# IAS_v005.net
KiCad netlist of a schematic drawn in EAGLE
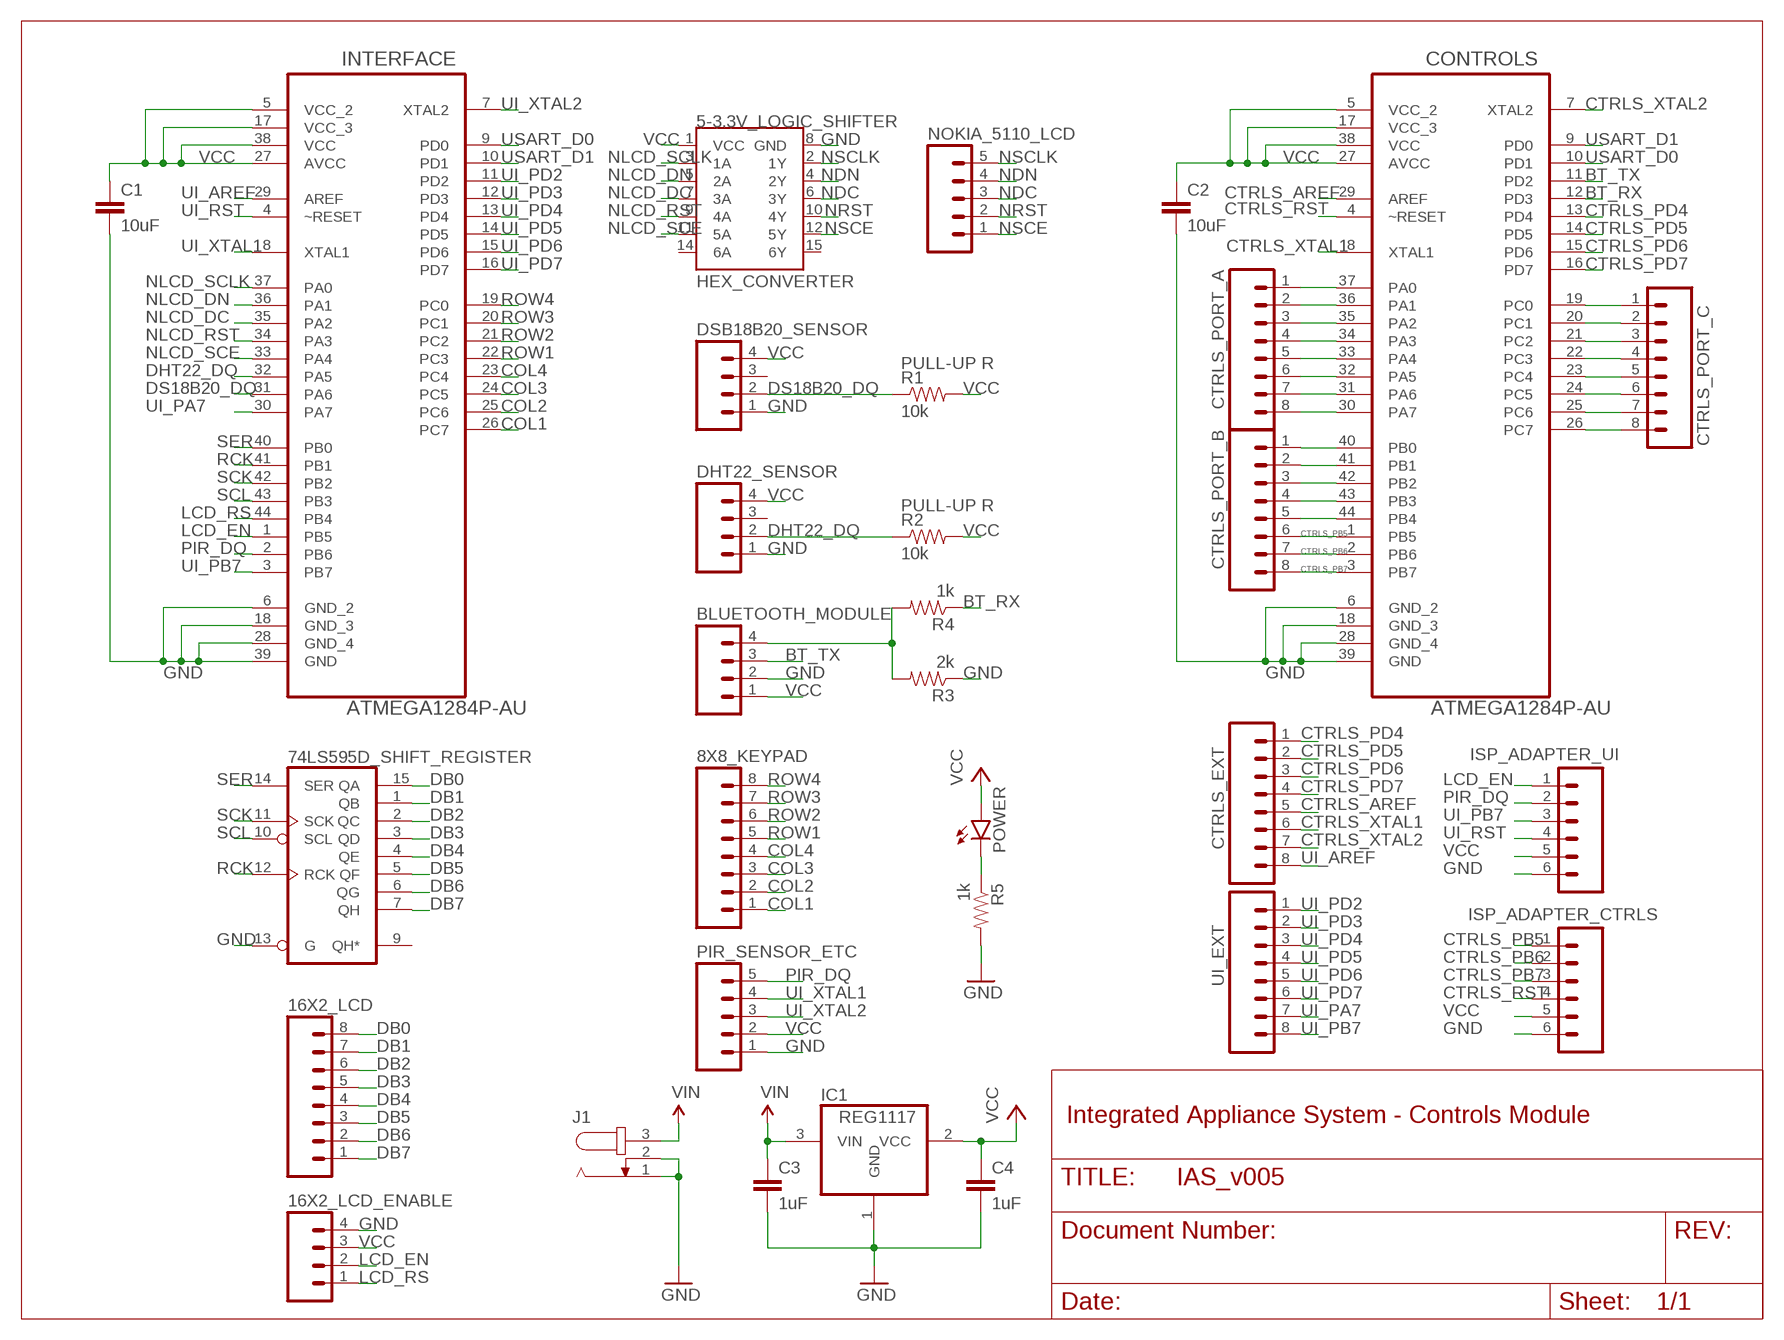
[diagram p0: schematic, sheet 1]

(export (version "E")
  (design (tool "Eeschema 10.0.6"))
  (components
    (comp (ref "5-3.3V_LOGIC_SHIFTER")
      (value "HEX_CONVERTER")
      (footprint "eagle-import:SO016")
      (fields (field (name "MPN") "74HC4050D,652"))
      (libsource (lib "eagle-import") (part "HEX_CONVERTER"))
    )
    (comp (ref "8X8_KEYPAD")
      (value "M08")
      (footprint "eagle-import:1X08_ROUND")
      (libsource (lib "eagle-import") (part "M08"))
    )
    (comp (ref "16X2_LCD")
      (value "M08")
      (footprint "eagle-import:1X08_ROUND")
      (libsource (lib "eagle-import") (part "M08"))
    )
    (comp (ref "16X2_LCD_ENABLE")
      (value "M04NO_SILK_ALL_ROUND")
      (footprint "eagle-import:1X04_NO_SILK_ALL_ROUND")
      (libsource (lib "eagle-import") (part "M04NO_SILK_ALL_ROUND"))
    )
    (comp (ref "74LS595D_SHIFT_REGISTER")
      (value "74LS595D")
      (footprint "eagle-import:SO16")
      (fields (field (name "MPN") "SN74LS595D"))
      (libsource (lib "eagle-import") (part "74595DLS"))
    )
    (comp (ref "BLUETOOTH_MODULE")
      (value "M04NO_SILK_ALL_ROUND")
      (footprint "eagle-import:1X04_NO_SILK_ALL_ROUND")
      (libsource (lib "eagle-import") (part "M04NO_SILK_ALL_ROUND"))
    )
    (comp (ref "C1")
      (value "10uF")
      (footprint "eagle-import:1206")
      (libsource (lib "eagle-import") (part "CAP1206"))
    )
    (comp (ref "C2")
      (value "10uF")
      (footprint "eagle-import:1206")
      (libsource (lib "eagle-import") (part "CAP1206"))
    )
    (comp (ref "C3")
      (value "1uF")
      (footprint "eagle-import:1206")
      (libsource (lib "eagle-import") (part "CAP1206"))
    )
    (comp (ref "C4")
      (value "1uF")
      (footprint "eagle-import:1206")
      (libsource (lib "eagle-import") (part "CAP1206"))
    )
    (comp (ref "CONTROLS")
      (value "ATMEGA1284P-AU")
      (footprint "eagle-import:QFP80P1200X1200X120-44N")
      (fields (field (name "OC_NEWARK") "unknown"))
      (libsource (lib "eagle-import") (part "ATMEGA1284P-AU"))
    )
    (comp (ref "CTRLS_EXT")
      (value "M08")
      (footprint "eagle-import:1X08_ROUND")
      (libsource (lib "eagle-import") (part "M08"))
    )
    (comp (ref "CTRLS_PORT_A")
      (value "M08")
      (footprint "eagle-import:1X08_ROUND")
      (libsource (lib "eagle-import") (part "M08"))
    )
    (comp (ref "CTRLS_PORT_B")
      (value "M08")
      (footprint "eagle-import:1X08_ROUND")
      (libsource (lib "eagle-import") (part "M08"))
    )
    (comp (ref "CTRLS_PORT_C")
      (value "M08")
      (footprint "eagle-import:1X08_ROUND")
      (libsource (lib "eagle-import") (part "M08"))
    )
    (comp (ref "DHT22_SENSOR")
      (value "M04NO_SILK_ALL_ROUND")
      (footprint "eagle-import:1X04_NO_SILK_ALL_ROUND")
      (libsource (lib "eagle-import") (part "M04NO_SILK_ALL_ROUND"))
    )
    (comp (ref "DSB18B20_SENSOR")
      (value "M04NO_SILK_ALL_ROUND")
      (footprint "eagle-import:1X04_NO_SILK_ALL_ROUND")
      (libsource (lib "eagle-import") (part "M04NO_SILK_ALL_ROUND"))
    )
    (comp (ref "IC1")
      (value "REG1117")
      (footprint "eagle-import:SOT223")
      (libsource (lib "eagle-import") (part "REG1117"))
    )
    (comp (ref "INTERFACE")
      (value "ATMEGA1284P-AU")
      (footprint "eagle-import:QFP80P1200X1200X120-44N")
      (fields (field (name "OC_NEWARK") "unknown"))
      (libsource (lib "eagle-import") (part "ATMEGA1284P-AU"))
    )
    (comp (ref "ISP_ADAPTER_CTRLS")
      (value "M06SILK_FEMALE_PTH")
      (footprint "eagle-import:1X06")
      (libsource (lib "eagle-import") (part "M06SILK_FEMALE_PTH"))
    )
    (comp (ref "ISP_ADAPTER_UI")
      (value "M06SILK_FEMALE_PTH")
      (footprint "eagle-import:1X06")
      (libsource (lib "eagle-import") (part "M06SILK_FEMALE_PTH"))
    )
    (comp (ref "J1")
      (value "JACK-PLUG0")
      (footprint "eagle-import:SPC4077")
      (libsource (lib "eagle-import") (part "JACK-PLUG0"))
    )
    (comp (ref "NOKIA_5110_LCD")
      (value "M05PTH")
      (footprint "eagle-import:1X05")
      (libsource (lib "eagle-import") (part "M05PTH"))
    )
    (comp (ref "PIR_SENSOR_ETC")
      (value "M05PTH")
      (footprint "eagle-import:1X05")
      (libsource (lib "eagle-import") (part "M05PTH"))
    )
    (comp (ref "POWER")
      (value "LED3MM")
      (footprint "eagle-import:LED3MM")
      (libsource (lib "eagle-import") (part "LED3MM"))
    )
    (comp (ref "R1")
      (value "10k")
      (footprint "eagle-import:1206")
      (libsource (lib "eagle-import") (part "RESISTOR1206"))
    )
    (comp (ref "R2")
      (value "10k")
      (footprint "eagle-import:1206")
      (libsource (lib "eagle-import") (part "RESISTOR1206"))
    )
    (comp (ref "R3")
      (value "2k")
      (footprint "eagle-import:1206")
      (libsource (lib "eagle-import") (part "RESISTOR1206"))
    )
    (comp (ref "R4")
      (value "1k")
      (footprint "eagle-import:1206")
      (libsource (lib "eagle-import") (part "RESISTOR1206"))
    )
    (comp (ref "R5")
      (value "1k")
      (footprint "eagle-import:1206")
      (libsource (lib "eagle-import") (part "RESISTOR1206"))
    )
    (comp (ref "UI_EXT")
      (value "M08")
      (footprint "eagle-import:1X08_ROUND")
      (libsource (lib "eagle-import") (part "M08"))
    )
  )
  (nets
    (net (code "1") (name "/BT_RX") (class "Default")
      (node (ref "CONTROLS") (pin "12") (pinfunction "PD3_12") (pintype "bidirectional"))
      (node (ref "R4") (pin "1") (pinfunction "1_1") (pintype "passive"))
    )
    (net (code "2") (name "/BT_TX") (class "Default")
      (node (ref "BLUETOOTH_MODULE") (pin "3") (pinfunction "3_3") (pintype "passive"))
      (node (ref "CONTROLS") (pin "11") (pinfunction "PD2_11") (pintype "bidirectional"))
    )
    (net (code "3") (name "/COL1") (class "Default")
      (node (ref "8X8_KEYPAD") (pin "1") (pinfunction "1_1") (pintype "passive"))
      (node (ref "INTERFACE") (pin "26") (pinfunction "PC7_26") (pintype "bidirectional"))
    )
    (net (code "4") (name "/COL2") (class "Default")
      (node (ref "8X8_KEYPAD") (pin "2") (pinfunction "2_2") (pintype "passive"))
      (node (ref "INTERFACE") (pin "25") (pinfunction "PC6_25") (pintype "bidirectional"))
    )
    (net (code "5") (name "/COL3") (class "Default")
      (node (ref "8X8_KEYPAD") (pin "3") (pinfunction "3_3") (pintype "passive"))
      (node (ref "INTERFACE") (pin "24") (pinfunction "PC5_24") (pintype "bidirectional"))
    )
    (net (code "6") (name "/COL4") (class "Default")
      (node (ref "8X8_KEYPAD") (pin "4") (pinfunction "4_4") (pintype "passive"))
      (node (ref "INTERFACE") (pin "23") (pinfunction "PC4_23") (pintype "bidirectional"))
    )
    (net (code "7") (name "/CTRLS_AREF") (class "Default")
      (node (ref "CONTROLS") (pin "29") (pinfunction "AREF_29") (pintype "input"))
      (node (ref "CTRLS_EXT") (pin "5") (pinfunction "5_5") (pintype "passive"))
    )
    (net (code "8") (name "/CTRLS_PB5") (class "Default")
      (node (ref "CONTROLS") (pin "1") (pinfunction "PB5_1") (pintype "bidirectional"))
      (node (ref "CTRLS_PORT_B") (pin "6") (pinfunction "6_6") (pintype "passive"))
      (node (ref "ISP_ADAPTER_CTRLS") (pin "1") (pinfunction "1_1") (pintype "passive"))
    )
    (net (code "9") (name "/CTRLS_PB6") (class "Default")
      (node (ref "CONTROLS") (pin "2") (pinfunction "PB6_2") (pintype "bidirectional"))
      (node (ref "CTRLS_PORT_B") (pin "7") (pinfunction "7_7") (pintype "passive"))
      (node (ref "ISP_ADAPTER_CTRLS") (pin "2") (pinfunction "2_2") (pintype "passive"))
    )
    (net (code "10") (name "/CTRLS_PB7") (class "Default")
      (node (ref "CONTROLS") (pin "3") (pinfunction "PB7_3") (pintype "bidirectional"))
      (node (ref "CTRLS_PORT_B") (pin "8") (pinfunction "8_8") (pintype "passive"))
      (node (ref "ISP_ADAPTER_CTRLS") (pin "3") (pinfunction "3_3") (pintype "passive"))
    )
    (net (code "11") (name "/CTRLS_PD4") (class "Default")
      (node (ref "CONTROLS") (pin "13") (pinfunction "PD4_13") (pintype "bidirectional"))
      (node (ref "CTRLS_EXT") (pin "1") (pinfunction "1_1") (pintype "passive"))
    )
    (net (code "12") (name "/CTRLS_PD5") (class "Default")
      (node (ref "CONTROLS") (pin "14") (pinfunction "PD5_14") (pintype "bidirectional"))
      (node (ref "CTRLS_EXT") (pin "2") (pinfunction "2_2") (pintype "passive"))
    )
    (net (code "13") (name "/CTRLS_PD6") (class "Default")
      (node (ref "CONTROLS") (pin "15") (pinfunction "PD6_15") (pintype "bidirectional"))
      (node (ref "CTRLS_EXT") (pin "3") (pinfunction "3_3") (pintype "passive"))
    )
    (net (code "14") (name "/CTRLS_PD7") (class "Default")
      (node (ref "CONTROLS") (pin "16") (pinfunction "PD7_16") (pintype "bidirectional"))
      (node (ref "CTRLS_EXT") (pin "4") (pinfunction "4_4") (pintype "passive"))
    )
    (net (code "15") (name "/CTRLS_RST") (class "Default")
      (node (ref "CONTROLS") (pin "4") (pinfunction "~{RESET}_4") (pintype "input"))
      (node (ref "ISP_ADAPTER_CTRLS") (pin "4") (pinfunction "4_4") (pintype "passive"))
    )
    (net (code "16") (name "/CTRLS_XTAL1") (class "Default")
      (node (ref "CONTROLS") (pin "8") (pinfunction "XTAL1_8") (pintype "input"))
      (node (ref "CTRLS_EXT") (pin "6") (pinfunction "6_6") (pintype "passive"))
    )
    (net (code "17") (name "/CTRLS_XTAL2") (class "Default")
      (node (ref "CONTROLS") (pin "7") (pinfunction "XTAL2_7") (pintype "output"))
      (node (ref "CTRLS_EXT") (pin "7") (pinfunction "7_7") (pintype "passive"))
    )
    (net (code "18") (name "/DB0") (class "Default")
      (node (ref "16X2_LCD") (pin "8") (pinfunction "8_8") (pintype "passive"))
      (node (ref "74LS595D_SHIFT_REGISTER") (pin "15") (pinfunction "QA_15") (pintype "tri_state"))
    )
    (net (code "19") (name "/DB1") (class "Default")
      (node (ref "16X2_LCD") (pin "7") (pinfunction "7_7") (pintype "passive"))
      (node (ref "74LS595D_SHIFT_REGISTER") (pin "1") (pinfunction "QB_1") (pintype "tri_state"))
    )
    (net (code "20") (name "/DB2") (class "Default")
      (node (ref "16X2_LCD") (pin "6") (pinfunction "6_6") (pintype "passive"))
      (node (ref "74LS595D_SHIFT_REGISTER") (pin "2") (pinfunction "QC_2") (pintype "tri_state"))
    )
    (net (code "21") (name "/DB3") (class "Default")
      (node (ref "16X2_LCD") (pin "5") (pinfunction "5_5") (pintype "passive"))
      (node (ref "74LS595D_SHIFT_REGISTER") (pin "3") (pinfunction "QD_3") (pintype "tri_state"))
    )
    (net (code "22") (name "/DB4") (class "Default")
      (node (ref "16X2_LCD") (pin "4") (pinfunction "4_4") (pintype "passive"))
      (node (ref "74LS595D_SHIFT_REGISTER") (pin "4") (pinfunction "QE_4") (pintype "tri_state"))
    )
    (net (code "23") (name "/DB5") (class "Default")
      (node (ref "16X2_LCD") (pin "3") (pinfunction "3_3") (pintype "passive"))
      (node (ref "74LS595D_SHIFT_REGISTER") (pin "5") (pinfunction "QF_5") (pintype "tri_state"))
    )
    (net (code "24") (name "/DB6") (class "Default")
      (node (ref "16X2_LCD") (pin "2") (pinfunction "2_2") (pintype "passive"))
      (node (ref "74LS595D_SHIFT_REGISTER") (pin "6") (pinfunction "QG_6") (pintype "tri_state"))
    )
    (net (code "25") (name "/DB7") (class "Default")
      (node (ref "16X2_LCD") (pin "1") (pinfunction "1_1") (pintype "passive"))
      (node (ref "74LS595D_SHIFT_REGISTER") (pin "7") (pinfunction "QH_7") (pintype "tri_state"))
    )
    (net (code "26") (name "/DHT22_DQ") (class "Default")
      (node (ref "DHT22_SENSOR") (pin "2") (pinfunction "2_2") (pintype "passive"))
      (node (ref "INTERFACE") (pin "32") (pinfunction "PA5_32") (pintype "bidirectional"))
      (node (ref "R2") (pin "1") (pinfunction "1_1") (pintype "passive"))
    )
    (net (code "27") (name "/DS18B20_DQ") (class "Default")
      (node (ref "DSB18B20_SENSOR") (pin "2") (pinfunction "2_2") (pintype "passive"))
      (node (ref "INTERFACE") (pin "31") (pinfunction "PA6_31") (pintype "bidirectional"))
      (node (ref "R1") (pin "1") (pinfunction "1_1") (pintype "passive"))
    )
    (net (code "28") (name "/LCD_EN") (class "Default")
      (node (ref "16X2_LCD_ENABLE") (pin "2") (pinfunction "2_2") (pintype "passive"))
      (node (ref "INTERFACE") (pin "1") (pinfunction "PB5_1") (pintype "bidirectional"))
      (node (ref "ISP_ADAPTER_UI") (pin "1") (pinfunction "1_1") (pintype "passive"))
    )
    (net (code "29") (name "/LCD_RS") (class "Default")
      (node (ref "16X2_LCD_ENABLE") (pin "1") (pinfunction "1_1") (pintype "passive"))
      (node (ref "INTERFACE") (pin "44") (pinfunction "PB4_44") (pintype "bidirectional"))
    )
    (net (code "30") (name "/NDC") (class "Default")
      (node (ref "5-3.3V_LOGIC_SHIFTER") (pin "6") (pinfunction "3Y_6") (pintype "bidirectional"))
      (node (ref "NOKIA_5110_LCD") (pin "3") (pinfunction "3_3") (pintype "passive"))
    )
    (net (code "31") (name "/NDN") (class "Default")
      (node (ref "5-3.3V_LOGIC_SHIFTER") (pin "4") (pinfunction "2Y_4") (pintype "bidirectional"))
      (node (ref "NOKIA_5110_LCD") (pin "4") (pinfunction "4_4") (pintype "passive"))
    )
    (net (code "32") (name "/NLCD_DC") (class "Default")
      (node (ref "5-3.3V_LOGIC_SHIFTER") (pin "7") (pinfunction "3A_7") (pintype "bidirectional"))
      (node (ref "INTERFACE") (pin "35") (pinfunction "PA2_35") (pintype "bidirectional"))
    )
    (net (code "33") (name "/NLCD_DN") (class "Default")
      (node (ref "5-3.3V_LOGIC_SHIFTER") (pin "5") (pinfunction "2A_5") (pintype "bidirectional"))
      (node (ref "INTERFACE") (pin "36") (pinfunction "PA1_36") (pintype "bidirectional"))
    )
    (net (code "34") (name "/NLCD_RST") (class "Default")
      (node (ref "5-3.3V_LOGIC_SHIFTER") (pin "9") (pinfunction "4A_9") (pintype "bidirectional"))
      (node (ref "INTERFACE") (pin "34") (pinfunction "PA3_34") (pintype "bidirectional"))
    )
    (net (code "35") (name "/NLCD_SCE") (class "Default")
      (node (ref "5-3.3V_LOGIC_SHIFTER") (pin "11") (pinfunction "5A_11") (pintype "bidirectional"))
      (node (ref "INTERFACE") (pin "33") (pinfunction "PA4_33") (pintype "bidirectional"))
    )
    (net (code "36") (name "/NLCD_SCLK") (class "Default")
      (node (ref "5-3.3V_LOGIC_SHIFTER") (pin "3") (pinfunction "1A_3") (pintype "bidirectional"))
      (node (ref "INTERFACE") (pin "37") (pinfunction "PA0_37") (pintype "bidirectional"))
    )
    (net (code "37") (name "/NRST") (class "Default")
      (node (ref "5-3.3V_LOGIC_SHIFTER") (pin "10") (pinfunction "4Y_10") (pintype "bidirectional"))
      (node (ref "NOKIA_5110_LCD") (pin "2") (pinfunction "2_2") (pintype "passive"))
    )
    (net (code "38") (name "/NSCE") (class "Default")
      (node (ref "5-3.3V_LOGIC_SHIFTER") (pin "12") (pinfunction "5Y_12") (pintype "bidirectional"))
      (node (ref "NOKIA_5110_LCD") (pin "1") (pinfunction "1_1") (pintype "passive"))
    )
    (net (code "39") (name "/NSCLK") (class "Default")
      (node (ref "5-3.3V_LOGIC_SHIFTER") (pin "2") (pinfunction "1Y_2") (pintype "bidirectional"))
      (node (ref "NOKIA_5110_LCD") (pin "5") (pinfunction "5_5") (pintype "passive"))
    )
    (net (code "40") (name "/PIR_DQ") (class "Default")
      (node (ref "INTERFACE") (pin "2") (pinfunction "PB6_2") (pintype "bidirectional"))
      (node (ref "ISP_ADAPTER_UI") (pin "2") (pinfunction "2_2") (pintype "passive"))
      (node (ref "PIR_SENSOR_ETC") (pin "5") (pinfunction "5_5") (pintype "passive"))
    )
    (net (code "41") (name "/RCK") (class "Default")
      (node (ref "74LS595D_SHIFT_REGISTER") (pin "12") (pinfunction "RCK_12") (pintype "input"))
      (node (ref "INTERFACE") (pin "41") (pinfunction "PB1_41") (pintype "bidirectional"))
    )
    (net (code "42") (name "/ROW1") (class "Default")
      (node (ref "8X8_KEYPAD") (pin "5") (pinfunction "5_5") (pintype "passive"))
      (node (ref "INTERFACE") (pin "22") (pinfunction "PC3_22") (pintype "bidirectional"))
    )
    (net (code "43") (name "/ROW2") (class "Default")
      (node (ref "8X8_KEYPAD") (pin "6") (pinfunction "6_6") (pintype "passive"))
      (node (ref "INTERFACE") (pin "21") (pinfunction "PC2_21") (pintype "bidirectional"))
    )
    (net (code "44") (name "/ROW3") (class "Default")
      (node (ref "8X8_KEYPAD") (pin "7") (pinfunction "7_7") (pintype "passive"))
      (node (ref "INTERFACE") (pin "20") (pinfunction "PC1_20") (pintype "bidirectional"))
    )
    (net (code "45") (name "/ROW4") (class "Default")
      (node (ref "8X8_KEYPAD") (pin "8") (pinfunction "8_8") (pintype "passive"))
      (node (ref "INTERFACE") (pin "19") (pinfunction "PC0_19") (pintype "bidirectional"))
    )
    (net (code "46") (name "/SCK") (class "Default")
      (node (ref "74LS595D_SHIFT_REGISTER") (pin "11") (pinfunction "SCK_11") (pintype "input"))
      (node (ref "INTERFACE") (pin "42") (pinfunction "PB2_42") (pintype "bidirectional"))
    )
    (net (code "47") (name "/SCL") (class "Default")
      (node (ref "74LS595D_SHIFT_REGISTER") (pin "10") (pinfunction "SCL_10") (pintype "input"))
      (node (ref "INTERFACE") (pin "43") (pinfunction "PB3_43") (pintype "bidirectional"))
    )
    (net (code "48") (name "/SER") (class "Default")
      (node (ref "74LS595D_SHIFT_REGISTER") (pin "14") (pinfunction "SER_14") (pintype "input"))
      (node (ref "INTERFACE") (pin "40") (pinfunction "PB0_40") (pintype "bidirectional"))
    )
    (net (code "49") (name "/UI_AREF") (class "Default")
      (node (ref "CTRLS_EXT") (pin "8") (pinfunction "8_8") (pintype "passive"))
      (node (ref "INTERFACE") (pin "29") (pinfunction "AREF_29") (pintype "input"))
    )
    (net (code "50") (name "/UI_PA7") (class "Default")
      (node (ref "INTERFACE") (pin "30") (pinfunction "PA7_30") (pintype "bidirectional"))
      (node (ref "UI_EXT") (pin "7") (pinfunction "7_7") (pintype "passive"))
    )
    (net (code "51") (name "/UI_PB7") (class "Default")
      (node (ref "INTERFACE") (pin "3") (pinfunction "PB7_3") (pintype "bidirectional"))
      (node (ref "ISP_ADAPTER_UI") (pin "3") (pinfunction "3_3") (pintype "passive"))
      (node (ref "UI_EXT") (pin "8") (pinfunction "8_8") (pintype "passive"))
    )
    (net (code "52") (name "/UI_PD2") (class "Default")
      (node (ref "INTERFACE") (pin "11") (pinfunction "PD2_11") (pintype "bidirectional"))
      (node (ref "UI_EXT") (pin "1") (pinfunction "1_1") (pintype "passive"))
    )
    (net (code "53") (name "/UI_PD3") (class "Default")
      (node (ref "INTERFACE") (pin "12") (pinfunction "PD3_12") (pintype "bidirectional"))
      (node (ref "UI_EXT") (pin "2") (pinfunction "2_2") (pintype "passive"))
    )
    (net (code "54") (name "/UI_PD4") (class "Default")
      (node (ref "INTERFACE") (pin "13") (pinfunction "PD4_13") (pintype "bidirectional"))
      (node (ref "UI_EXT") (pin "3") (pinfunction "3_3") (pintype "passive"))
    )
    (net (code "55") (name "/UI_PD5") (class "Default")
      (node (ref "INTERFACE") (pin "14") (pinfunction "PD5_14") (pintype "bidirectional"))
      (node (ref "UI_EXT") (pin "4") (pinfunction "4_4") (pintype "passive"))
    )
    (net (code "56") (name "/UI_PD6") (class "Default")
      (node (ref "INTERFACE") (pin "15") (pinfunction "PD6_15") (pintype "bidirectional"))
      (node (ref "UI_EXT") (pin "5") (pinfunction "5_5") (pintype "passive"))
    )
    (net (code "57") (name "/UI_PD7") (class "Default")
      (node (ref "INTERFACE") (pin "16") (pinfunction "PD7_16") (pintype "bidirectional"))
      (node (ref "UI_EXT") (pin "6") (pinfunction "6_6") (pintype "passive"))
    )
    (net (code "58") (name "/UI_RST") (class "Default")
      (node (ref "INTERFACE") (pin "4") (pinfunction "~{RESET}_4") (pintype "input"))
      (node (ref "ISP_ADAPTER_UI") (pin "4") (pinfunction "4_4") (pintype "passive"))
    )
    (net (code "59") (name "/UI_XTAL1") (class "Default")
      (node (ref "INTERFACE") (pin "8") (pinfunction "XTAL1_8") (pintype "input"))
      (node (ref "PIR_SENSOR_ETC") (pin "4") (pinfunction "4_4") (pintype "passive"))
    )
    (net (code "60") (name "/UI_XTAL2") (class "Default")
      (node (ref "INTERFACE") (pin "7") (pinfunction "XTAL2_7") (pintype "output"))
      (node (ref "PIR_SENSOR_ETC") (pin "3") (pinfunction "3_3") (pintype "passive"))
    )
    (net (code "61") (name "/USART_D0") (class "Default")
      (node (ref "CONTROLS") (pin "10") (pinfunction "PD1_10") (pintype "bidirectional"))
      (node (ref "INTERFACE") (pin "9") (pinfunction "PD0_9") (pintype "bidirectional"))
    )
    (net (code "62") (name "/USART_D1") (class "Default")
      (node (ref "CONTROLS") (pin "9") (pinfunction "PD0_9") (pintype "bidirectional"))
      (node (ref "INTERFACE") (pin "10") (pinfunction "PD1_10") (pintype "bidirectional"))
    )
    (net (code "63") (name "GND") (class "Default")
      (node (ref "16X2_LCD_ENABLE") (pin "4") (pinfunction "4_4") (pintype "passive"))
      (node (ref "5-3.3V_LOGIC_SHIFTER") (pin "8") (pinfunction "GND_8") (pintype "bidirectional"))
      (node (ref "74LS595D_SHIFT_REGISTER") (pin "13") (pinfunction "G_13") (pintype "input"))
      (node (ref "BLUETOOTH_MODULE") (pin "2") (pinfunction "2_2") (pintype "passive"))
      (node (ref "C1") (pin "2") (pinfunction "2_2") (pintype "passive"))
      (node (ref "C2") (pin "2") (pinfunction "2_2") (pintype "passive"))
      (node (ref "C3") (pin "2") (pinfunction "2_2") (pintype "passive"))
      (node (ref "C4") (pin "2") (pinfunction "2_2") (pintype "passive"))
      (node (ref "CONTROLS") (pin "18") (pinfunction "GND_3_18") (pintype "passive"))
      (node (ref "CONTROLS") (pin "28") (pinfunction "GND_4_28") (pintype "passive"))
      (node (ref "CONTROLS") (pin "39") (pinfunction "GND_39") (pintype "passive"))
      (node (ref "CONTROLS") (pin "6") (pinfunction "GND_2_6") (pintype "passive"))
      (node (ref "DHT22_SENSOR") (pin "1") (pinfunction "1_1") (pintype "passive"))
      (node (ref "DSB18B20_SENSOR") (pin "1") (pinfunction "1_1") (pintype "passive"))
      (node (ref "IC1") (pin "1") (pinfunction "GND_1") (pintype "power_in"))
      (node (ref "INTERFACE") (pin "18") (pinfunction "GND_3_18") (pintype "passive"))
      (node (ref "INTERFACE") (pin "28") (pinfunction "GND_4_28") (pintype "passive"))
      (node (ref "INTERFACE") (pin "39") (pinfunction "GND_39") (pintype "passive"))
      (node (ref "INTERFACE") (pin "6") (pinfunction "GND_2_6") (pintype "passive"))
      (node (ref "ISP_ADAPTER_CTRLS") (pin "6") (pinfunction "6_6") (pintype "passive"))
      (node (ref "ISP_ADAPTER_UI") (pin "6") (pinfunction "6_6") (pintype "passive"))
      (node (ref "J1") (pin "1") (pinfunction "1_1") (pintype "passive"))
      (node (ref "J1") (pin "2") (pinfunction "2_2") (pintype "passive"))
      (node (ref "PIR_SENSOR_ETC") (pin "1") (pinfunction "1_1") (pintype "passive"))
      (node (ref "R3") (pin "1") (pinfunction "1_1") (pintype "passive"))
      (node (ref "R5") (pin "2") (pinfunction "2_2") (pintype "passive"))
    )
    (net (code "64") (name "Net-(BLUETOOTH_MODULE-Pad4)") (class "Default")
      (node (ref "BLUETOOTH_MODULE") (pin "4") (pinfunction "4_4") (pintype "passive"))
      (node (ref "R3") (pin "2") (pinfunction "2_2") (pintype "passive"))
      (node (ref "R4") (pin "2") (pinfunction "2_2") (pintype "passive"))
    )
    (net (code "65") (name "Net-(CONTROLS-PA0)") (class "Default")
      (node (ref "CONTROLS") (pin "37") (pinfunction "PA0_37") (pintype "bidirectional"))
      (node (ref "CTRLS_PORT_A") (pin "1") (pinfunction "1_1") (pintype "passive"))
    )
    (net (code "66") (name "Net-(CONTROLS-PA1)") (class "Default")
      (node (ref "CONTROLS") (pin "36") (pinfunction "PA1_36") (pintype "bidirectional"))
      (node (ref "CTRLS_PORT_A") (pin "2") (pinfunction "2_2") (pintype "passive"))
    )
    (net (code "67") (name "Net-(CONTROLS-PA2)") (class "Default")
      (node (ref "CONTROLS") (pin "35") (pinfunction "PA2_35") (pintype "bidirectional"))
      (node (ref "CTRLS_PORT_A") (pin "3") (pinfunction "3_3") (pintype "passive"))
    )
    (net (code "68") (name "Net-(CONTROLS-PA3)") (class "Default")
      (node (ref "CONTROLS") (pin "34") (pinfunction "PA3_34") (pintype "bidirectional"))
      (node (ref "CTRLS_PORT_A") (pin "4") (pinfunction "4_4") (pintype "passive"))
    )
    (net (code "69") (name "Net-(CONTROLS-PA4)") (class "Default")
      (node (ref "CONTROLS") (pin "33") (pinfunction "PA4_33") (pintype "bidirectional"))
      (node (ref "CTRLS_PORT_A") (pin "5") (pinfunction "5_5") (pintype "passive"))
    )
    (net (code "70") (name "Net-(CONTROLS-PA5)") (class "Default")
      (node (ref "CONTROLS") (pin "32") (pinfunction "PA5_32") (pintype "bidirectional"))
      (node (ref "CTRLS_PORT_A") (pin "6") (pinfunction "6_6") (pintype "passive"))
    )
    (net (code "71") (name "Net-(CONTROLS-PA6)") (class "Default")
      (node (ref "CONTROLS") (pin "31") (pinfunction "PA6_31") (pintype "bidirectional"))
      (node (ref "CTRLS_PORT_A") (pin "7") (pinfunction "7_7") (pintype "passive"))
    )
    (net (code "72") (name "Net-(CONTROLS-PA7)") (class "Default")
      (node (ref "CONTROLS") (pin "30") (pinfunction "PA7_30") (pintype "bidirectional"))
      (node (ref "CTRLS_PORT_A") (pin "8") (pinfunction "8_8") (pintype "passive"))
    )
    (net (code "73") (name "Net-(CONTROLS-PB0)") (class "Default")
      (node (ref "CONTROLS") (pin "40") (pinfunction "PB0_40") (pintype "bidirectional"))
      (node (ref "CTRLS_PORT_B") (pin "1") (pinfunction "1_1") (pintype "passive"))
    )
    (net (code "74") (name "Net-(CONTROLS-PB1)") (class "Default")
      (node (ref "CONTROLS") (pin "41") (pinfunction "PB1_41") (pintype "bidirectional"))
      (node (ref "CTRLS_PORT_B") (pin "2") (pinfunction "2_2") (pintype "passive"))
    )
    (net (code "75") (name "Net-(CONTROLS-PB2)") (class "Default")
      (node (ref "CONTROLS") (pin "42") (pinfunction "PB2_42") (pintype "bidirectional"))
      (node (ref "CTRLS_PORT_B") (pin "3") (pinfunction "3_3") (pintype "passive"))
    )
    (net (code "76") (name "Net-(CONTROLS-PB3)") (class "Default")
      (node (ref "CONTROLS") (pin "43") (pinfunction "PB3_43") (pintype "bidirectional"))
      (node (ref "CTRLS_PORT_B") (pin "4") (pinfunction "4_4") (pintype "passive"))
    )
    (net (code "77") (name "Net-(CONTROLS-PB4)") (class "Default")
      (node (ref "CONTROLS") (pin "44") (pinfunction "PB4_44") (pintype "bidirectional"))
      (node (ref "CTRLS_PORT_B") (pin "5") (pinfunction "5_5") (pintype "passive"))
    )
    (net (code "78") (name "Net-(CONTROLS-PC0)") (class "Default")
      (node (ref "CONTROLS") (pin "19") (pinfunction "PC0_19") (pintype "bidirectional"))
      (node (ref "CTRLS_PORT_C") (pin "1") (pinfunction "1_1") (pintype "passive"))
    )
    (net (code "79") (name "Net-(CONTROLS-PC1)") (class "Default")
      (node (ref "CONTROLS") (pin "20") (pinfunction "PC1_20") (pintype "bidirectional"))
      (node (ref "CTRLS_PORT_C") (pin "2") (pinfunction "2_2") (pintype "passive"))
    )
    (net (code "80") (name "Net-(CONTROLS-PC2)") (class "Default")
      (node (ref "CONTROLS") (pin "21") (pinfunction "PC2_21") (pintype "bidirectional"))
      (node (ref "CTRLS_PORT_C") (pin "3") (pinfunction "3_3") (pintype "passive"))
    )
    (net (code "81") (name "Net-(CONTROLS-PC3)") (class "Default")
      (node (ref "CONTROLS") (pin "22") (pinfunction "PC3_22") (pintype "bidirectional"))
      (node (ref "CTRLS_PORT_C") (pin "4") (pinfunction "4_4") (pintype "passive"))
    )
    (net (code "82") (name "Net-(CONTROLS-PC4)") (class "Default")
      (node (ref "CONTROLS") (pin "23") (pinfunction "PC4_23") (pintype "bidirectional"))
      (node (ref "CTRLS_PORT_C") (pin "5") (pinfunction "5_5") (pintype "passive"))
    )
    (net (code "83") (name "Net-(CONTROLS-PC5)") (class "Default")
      (node (ref "CONTROLS") (pin "24") (pinfunction "PC5_24") (pintype "bidirectional"))
      (node (ref "CTRLS_PORT_C") (pin "6") (pinfunction "6_6") (pintype "passive"))
    )
    (net (code "84") (name "Net-(CONTROLS-PC6)") (class "Default")
      (node (ref "CONTROLS") (pin "25") (pinfunction "PC6_25") (pintype "bidirectional"))
      (node (ref "CTRLS_PORT_C") (pin "7") (pinfunction "7_7") (pintype "passive"))
    )
    (net (code "85") (name "Net-(CONTROLS-PC7)") (class "Default")
      (node (ref "CONTROLS") (pin "26") (pinfunction "PC7_26") (pintype "bidirectional"))
      (node (ref "CTRLS_PORT_C") (pin "8") (pinfunction "8_8") (pintype "passive"))
    )
    (net (code "86") (name "Net-(POWER-C)") (class "Default")
      (node (ref "POWER") (pin "K") (pinfunction "C_K") (pintype "passive"))
      (node (ref "R5") (pin "1") (pinfunction "1_1") (pintype "passive"))
    )
    (net (code "87") (name "VCC") (class "Default")
      (node (ref "16X2_LCD_ENABLE") (pin "3") (pinfunction "3_3") (pintype "passive"))
      (node (ref "5-3.3V_LOGIC_SHIFTER") (pin "1") (pinfunction "VCC_1") (pintype "bidirectional"))
      (node (ref "BLUETOOTH_MODULE") (pin "1") (pinfunction "1_1") (pintype "passive"))
      (node (ref "C1") (pin "1") (pinfunction "1_1") (pintype "passive"))
      (node (ref "C2") (pin "1") (pinfunction "1_1") (pintype "passive"))
      (node (ref "C4") (pin "1") (pinfunction "1_1") (pintype "passive"))
      (node (ref "CONTROLS") (pin "17") (pinfunction "VCC_3_17") (pintype "power_in"))
      (node (ref "CONTROLS") (pin "27") (pinfunction "AVCC_27") (pintype "power_in"))
      (node (ref "CONTROLS") (pin "38") (pinfunction "VCC_38") (pintype "power_in"))
      (node (ref "CONTROLS") (pin "5") (pinfunction "VCC_2_5") (pintype "power_in"))
      (node (ref "DHT22_SENSOR") (pin "4") (pinfunction "4_4") (pintype "passive"))
      (node (ref "DSB18B20_SENSOR") (pin "4") (pinfunction "4_4") (pintype "passive"))
      (node (ref "IC1") (pin "2") (pinfunction "VCC_2") (pintype "power_in"))
      (node (ref "INTERFACE") (pin "17") (pinfunction "VCC_3_17") (pintype "power_in"))
      (node (ref "INTERFACE") (pin "27") (pinfunction "AVCC_27") (pintype "power_in"))
      (node (ref "INTERFACE") (pin "38") (pinfunction "VCC_38") (pintype "power_in"))
      (node (ref "INTERFACE") (pin "5") (pinfunction "VCC_2_5") (pintype "power_in"))
      (node (ref "ISP_ADAPTER_CTRLS") (pin "5") (pinfunction "5_5") (pintype "passive"))
      (node (ref "ISP_ADAPTER_UI") (pin "5") (pinfunction "5_5") (pintype "passive"))
      (node (ref "PIR_SENSOR_ETC") (pin "2") (pinfunction "2_2") (pintype "passive"))
      (node (ref "POWER") (pin "A") (pinfunction "A_A") (pintype "passive"))
      (node (ref "R1") (pin "2") (pinfunction "2_2") (pintype "passive"))
      (node (ref "R2") (pin "2") (pinfunction "2_2") (pintype "passive"))
    )
    (net (code "88") (name "VIN") (class "Default")
      (node (ref "C3") (pin "1") (pinfunction "1_1") (pintype "passive"))
      (node (ref "IC1") (pin "3") (pinfunction "VIN_3") (pintype "input"))
      (node (ref "J1") (pin "3") (pinfunction "3_3") (pintype "passive"))
    )
    (net (code "89") (name "unconnected-(5-3.3V_LOGIC_SHIFTER-6A-Pad14)") (class "Default")
      (node (ref "5-3.3V_LOGIC_SHIFTER") (pin "14") (pinfunction "6A_14") (pintype "bidirectional"))
    )
    (net (code "90") (name "unconnected-(5-3.3V_LOGIC_SHIFTER-6Y-Pad15)") (class "Default")
      (node (ref "5-3.3V_LOGIC_SHIFTER") (pin "15") (pinfunction "6Y_15") (pintype "bidirectional"))
    )
    (net (code "91") (name "unconnected-(74LS595D_SHIFT_REGISTERA-QH*-Pad9)") (class "Default")
      (node (ref "74LS595D_SHIFT_REGISTER") (pin "9") (pinfunction "QH*_9") (pintype "tri_state"))
    )
    (net (code "92") (name "unconnected-(DHT22_SENSOR-Pad3)") (class "Default")
      (node (ref "DHT22_SENSOR") (pin "3") (pinfunction "3_3") (pintype "passive"))
    )
    (net (code "93") (name "unconnected-(DSB18B20_SENSOR-Pad3)") (class "Default")
      (node (ref "DSB18B20_SENSOR") (pin "3") (pinfunction "3_3") (pintype "passive"))
    )
  )
)
